# atlas_single.net
KiCad netlist of a schematic drawn in EAGLE
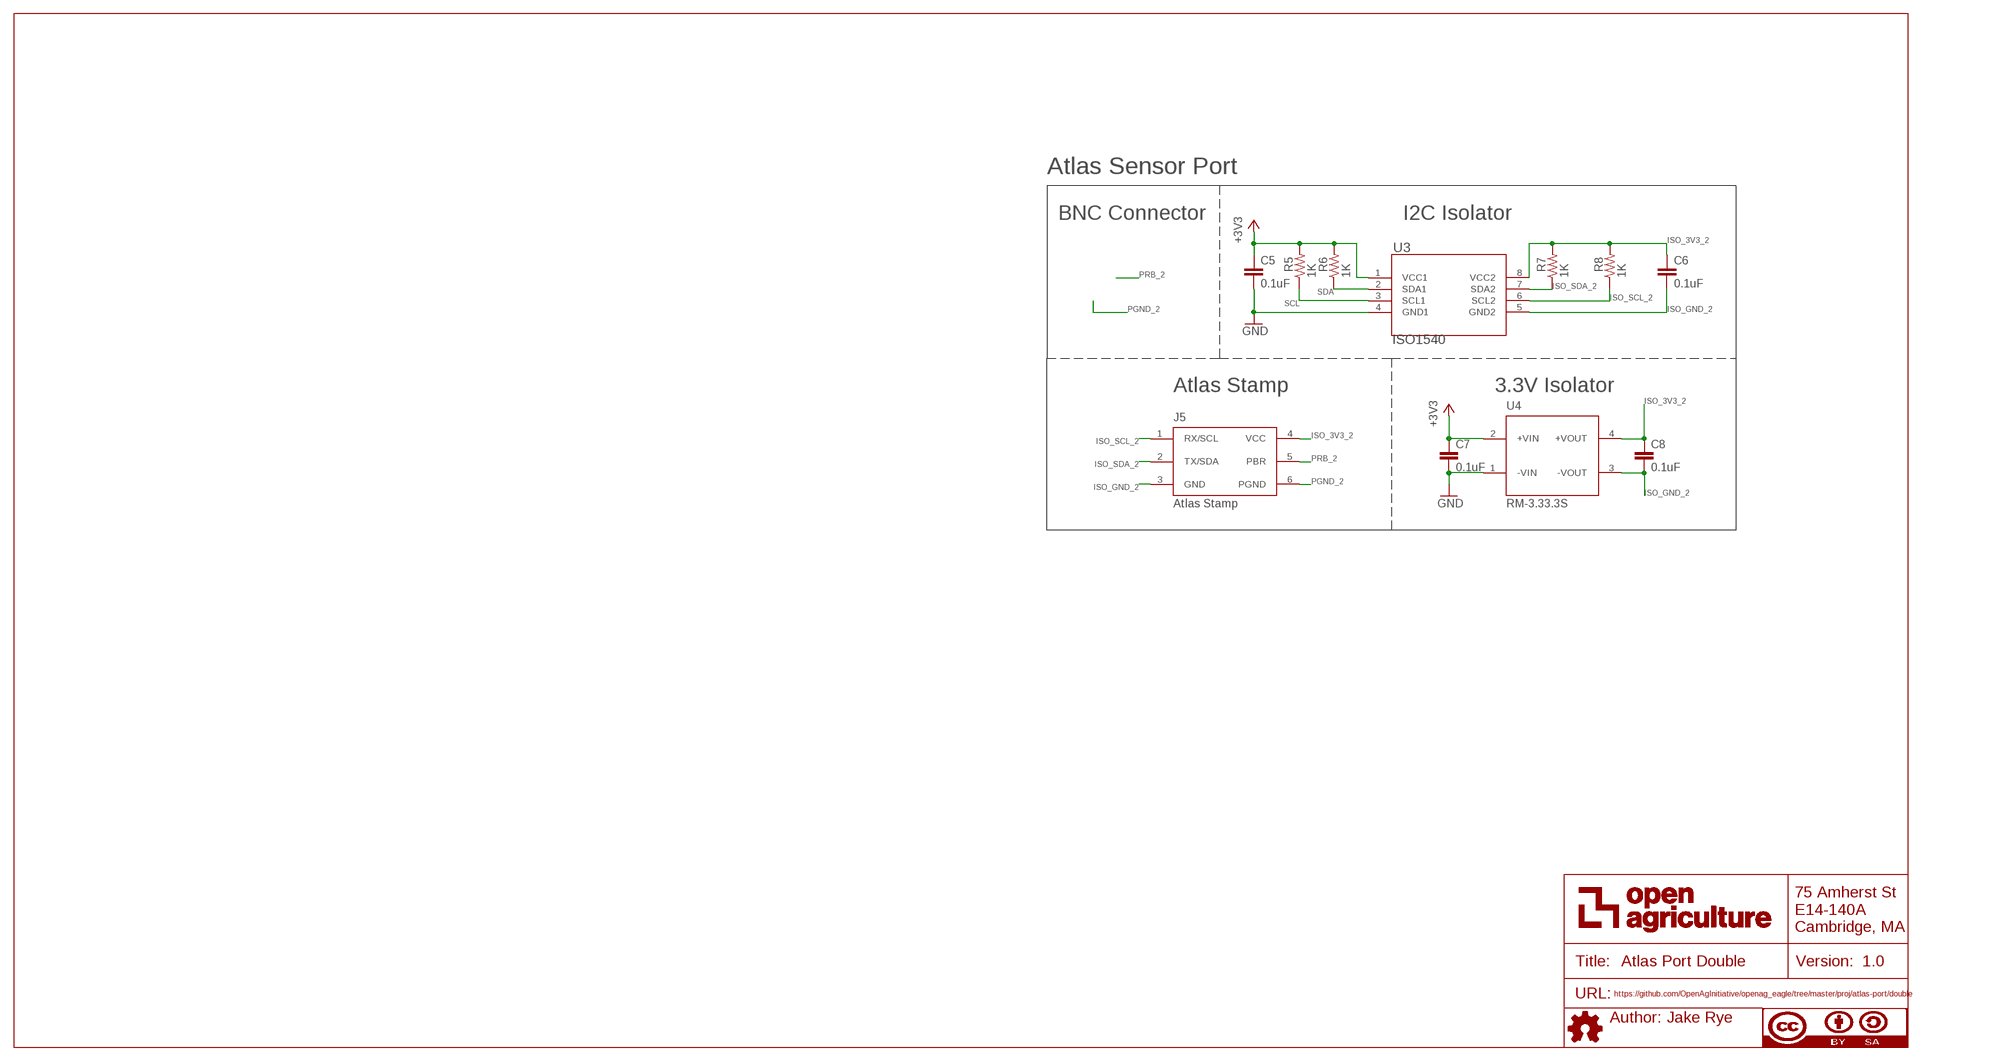
[diagram p0: schematic, sheet 1]

(export (version "E")
  (design (tool "Eeschema 10.0.6"))
  (components
    (comp (ref "C5")
      (value "0.1uF")
      (footprint "eagle-import:C0603")
      (fields (field (name "MANUFACTURER") "Kemet") (field (name "MPN") "C0603C104K5RACTU"))
      (libsource (lib "eagle-import") (part "0.1UF-C0603C104K5RACTU"))
    )
    (comp (ref "C6")
      (value "0.1uF")
      (footprint "eagle-import:C0603")
      (fields (field (name "MANUFACTURER") "Kemet") (field (name "MPN") "C0603C104K5RACTU"))
      (libsource (lib "eagle-import") (part "0.1UF-C0603C104K5RACTU"))
    )
    (comp (ref "C7")
      (value "0.1uF")
      (footprint "eagle-import:C0603")
      (fields (field (name "MANUFACTURER") "Kemet") (field (name "MPN") "C0603C104K5RACTU"))
      (libsource (lib "eagle-import") (part "0.1UF-C0603C104K5RACTU"))
    )
    (comp (ref "C8")
      (value "0.1uF")
      (footprint "eagle-import:C0603")
      (fields (field (name "MANUFACTURER") "Kemet") (field (name "MPN") "C0603C104K5RACTU"))
      (libsource (lib "eagle-import") (part "0.1UF-C0603C104K5RACTU"))
    )
    (comp (ref "J5")
      (value "Atlas Stamp")
      (footprint "eagle-import:ATLAS-STAMP")
      (libsource (lib "eagle-import") (part "ATLAS-STAMP"))
    )
    (comp (ref "R5")
      (value "1K")
      (footprint "eagle-import:RC0603N")
      (fields (field (name "MANUFACTURER") "Panasonic") (field (name "MPN") "P20283CT-ND"))
      (libsource (lib "eagle-import") (part "1K-ERJ-PB3D1001V"))
    )
    (comp (ref "R6")
      (value "1K")
      (footprint "eagle-import:RC0603N")
      (fields (field (name "MANUFACTURER") "Panasonic") (field (name "MPN") "P20283CT-ND"))
      (libsource (lib "eagle-import") (part "1K-ERJ-PB3D1001V"))
    )
    (comp (ref "R7")
      (value "1K")
      (footprint "eagle-import:RC0603N")
      (fields (field (name "MANUFACTURER") "Panasonic") (field (name "MPN") "P20283CT-ND"))
      (libsource (lib "eagle-import") (part "1K-ERJ-PB3D1001V"))
    )
    (comp (ref "R8")
      (value "1K")
      (footprint "eagle-import:RC0603N")
      (fields (field (name "MANUFACTURER") "Panasonic") (field (name "MPN") "P20283CT-ND"))
      (libsource (lib "eagle-import") (part "1K-ERJ-PB3D1001V"))
    )
    (comp (ref "U3")
      (value "ISO1540")
      (footprint "eagle-import:D8")
      (fields (field (name "MANUFACTURER") "Texas Instruments") (field (name "MPN") "ISO1540DR"))
      (libsource (lib "eagle-import") (part "ISO1540DR"))
    )
    (comp (ref "U4")
      (value "RM-3.33.3S")
      (footprint "eagle-import:RM3.33.3S-SIP4")
      (fields (field (name "MANUFACTURER") "Recom Power"))
      (libsource (lib "eagle-import") (part "RM3.33.3S"))
    )
  )
  (nets
    (net (code "1") (name "+3V3") (class "Default")
      (node (ref "C5") (pin "1") (pinfunction "1_1") (pintype "passive"))
      (node (ref "C7") (pin "1") (pinfunction "1_1") (pintype "passive"))
      (node (ref "R5") (pin "2") (pinfunction "2_2") (pintype "passive"))
      (node (ref "R6") (pin "2") (pinfunction "2_2") (pintype "passive"))
      (node (ref "U3") (pin "1") (pinfunction "VCC1_1") (pintype "power_in"))
      (node (ref "U4") (pin "2") (pinfunction "+VIN_2") (pintype "power_in"))
    )
    (net (code "2") (name "GND") (class "Default")
      (node (ref "C5") (pin "2") (pinfunction "2_2") (pintype "passive"))
      (node (ref "C7") (pin "2") (pinfunction "2_2") (pintype "passive"))
      (node (ref "U3") (pin "4") (pinfunction "GND1_4") (pintype "power_in"))
      (node (ref "U4") (pin "1") (pinfunction "-VIN_1") (pintype "power_in"))
    )
    (net (code "3") (name "ISO_3V3_2") (class "Default")
      (node (ref "C6") (pin "1") (pinfunction "1_1") (pintype "passive"))
      (node (ref "C8") (pin "1") (pinfunction "1_1") (pintype "passive"))
      (node (ref "J5") (pin "4") (pinfunction "VCC_4") (pintype "power_in"))
      (node (ref "R7") (pin "2") (pinfunction "2_2") (pintype "passive"))
      (node (ref "R8") (pin "2") (pinfunction "2_2") (pintype "passive"))
      (node (ref "U3") (pin "8") (pinfunction "VCC2_8") (pintype "power_in"))
      (node (ref "U4") (pin "4") (pinfunction "+VOUT_4") (pintype "power_in"))
    )
    (net (code "4") (name "ISO_GND_2") (class "Default")
      (node (ref "C6") (pin "2") (pinfunction "2_2") (pintype "passive"))
      (node (ref "C8") (pin "2") (pinfunction "2_2") (pintype "passive"))
      (node (ref "J5") (pin "3") (pinfunction "GND_3") (pintype "power_in"))
      (node (ref "U3") (pin "5") (pinfunction "GND2_5") (pintype "power_in"))
      (node (ref "U4") (pin "3") (pinfunction "-VOUT_3") (pintype "power_in"))
    )
    (net (code "5") (name "ISO_SCL_2") (class "Default")
      (node (ref "J5") (pin "1") (pinfunction "RX/SCL_1") (pintype "bidirectional"))
      (node (ref "R8") (pin "1") (pinfunction "1_1") (pintype "passive"))
      (node (ref "U3") (pin "6") (pinfunction "SCL2_6") (pintype "bidirectional"))
    )
    (net (code "6") (name "ISO_SDA_2") (class "Default")
      (node (ref "J5") (pin "2") (pinfunction "TX/SDA_2") (pintype "bidirectional"))
      (node (ref "R7") (pin "1") (pinfunction "1_1") (pintype "passive"))
      (node (ref "U3") (pin "7") (pinfunction "SDA2_7") (pintype "bidirectional"))
    )
    (net (code "7") (name "PGND_2") (class "Default")
      (node (ref "J5") (pin "6") (pinfunction "PGND_6") (pintype "power_in"))
    )
    (net (code "8") (name "PRB_2") (class "Default")
      (node (ref "J5") (pin "5") (pinfunction "PBR_5") (pintype "bidirectional"))
    )
    (net (code "9") (name "SCL") (class "Default")
      (node (ref "R5") (pin "1") (pinfunction "1_1") (pintype "passive"))
      (node (ref "U3") (pin "3") (pinfunction "SCL1_3") (pintype "bidirectional"))
    )
    (net (code "10") (name "SDA") (class "Default")
      (node (ref "R6") (pin "1") (pinfunction "1_1") (pintype "passive"))
      (node (ref "U3") (pin "2") (pinfunction "SDA1_2") (pintype "bidirectional"))
    )
  )
)
